# LUPA_uZED.net
KiCad netlist of a schematic drawn in EAGLE
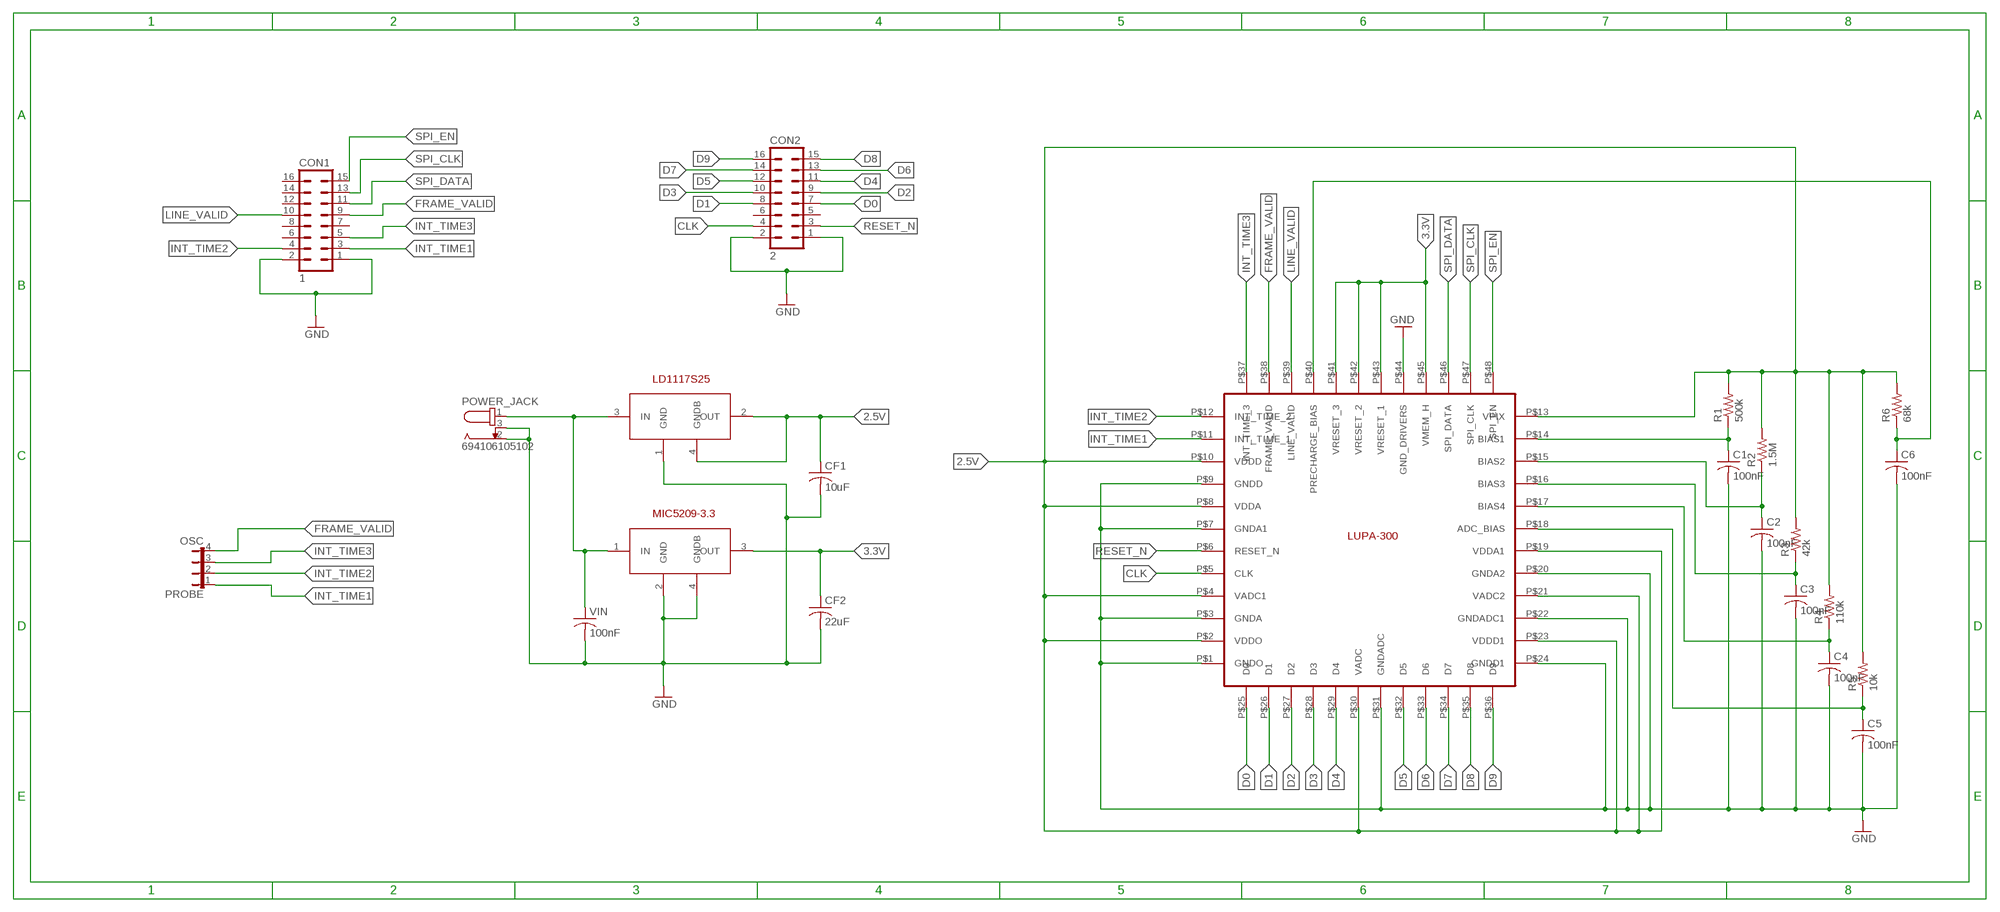
[diagram p0: schematic, sheet 1]

(export (version "E")
  (design (tool "Eeschema 10.0.6"))
  (components
    (comp (ref "C1")
      (value "100nF")
      (footprint "eagle-import:C3216")
      (libsource (lib "eagle-import") (part "C-USC3216"))
    )
    (comp (ref "C2")
      (value "100nF")
      (footprint "eagle-import:C3216")
      (libsource (lib "eagle-import") (part "C-USC3216"))
    )
    (comp (ref "C3")
      (value "100nF")
      (footprint "eagle-import:C3216")
      (libsource (lib "eagle-import") (part "C-USC3216"))
    )
    (comp (ref "C4")
      (value "100nF")
      (footprint "eagle-import:C3216")
      (libsource (lib "eagle-import") (part "C-USC3216"))
    )
    (comp (ref "C5")
      (value "100nF")
      (footprint "eagle-import:C3216")
      (libsource (lib "eagle-import") (part "C-USC3216"))
    )
    (comp (ref "C6")
      (value "100nF")
      (footprint "eagle-import:C3216")
      (libsource (lib "eagle-import") (part "C-USC3216"))
    )
    (comp (ref "CF1")
      (value "10uF")
      (footprint "eagle-import:C3216")
      (libsource (lib "eagle-import") (part "C-USC3216"))
    )
    (comp (ref "CF2")
      (value "22uF")
      (footprint "eagle-import:C3216")
      (libsource (lib "eagle-import") (part "C-USC3216"))
    )
    (comp (ref "CON1")
      (value "1")
      (footprint "eagle-import:MA08-2")
      (libsource (lib "eagle-import") (part "MA08-2"))
    )
    (comp (ref "CON2")
      (value "2")
      (footprint "eagle-import:MA08-2")
      (libsource (lib "eagle-import") (part "MA08-2"))
    )
    (comp (ref "POWER_JACK")
      (value "694106105102")
      (footprint "eagle-import:694106105102")
      (libsource (lib "eagle-import") (part "694106105102"))
    )
    (comp (ref "PROBE")
      (value "OSC")
      (footprint "eagle-import:JP4")
      (libsource (lib "eagle-import") (part "JP4E"))
    )
    (comp (ref "R1")
      (value "500k")
      (footprint "eagle-import:R1206")
      (libsource (lib "eagle-import") (part "R-US_R1206"))
    )
    (comp (ref "R2")
      (value "1.5M")
      (footprint "eagle-import:R1206")
      (libsource (lib "eagle-import") (part "R-US_R1206"))
    )
    (comp (ref "R3")
      (value "42k")
      (footprint "eagle-import:R1206")
      (libsource (lib "eagle-import") (part "R-US_R1206"))
    )
    (comp (ref "R4")
      (value "110k")
      (footprint "eagle-import:R1206")
      (libsource (lib "eagle-import") (part "R-US_R1206"))
    )
    (comp (ref "R5")
      (value "10k")
      (footprint "eagle-import:R1206")
      (libsource (lib "eagle-import") (part "R-US_R1206"))
    )
    (comp (ref "R6")
      (value "68k")
      (footprint "eagle-import:R1206")
      (libsource (lib "eagle-import") (part "R-US_R1206"))
    )
    (comp (ref "U$1")
      (value "IS")
      (footprint "eagle-import:LUPA300")
      (libsource (lib "eagle-import") (part "LUPA300"))
    )
    (comp (ref "U$2")
      (value "LD1117S25")
      (footprint "eagle-import:SOT223")
      (libsource (lib "eagle-import") (part "LD1117S25"))
    )
    (comp (ref "U$3")
      (value "MIC5209-3.3")
      (footprint "eagle-import:SOT223")
      (libsource (lib "eagle-import") (part "MIC5209-3.3"))
    )
    (comp (ref "VIN")
      (value "100nF")
      (footprint "eagle-import:C3216")
      (libsource (lib "eagle-import") (part "C-USC3216"))
    )
  )
  (nets
    (net (code "1") (name "2.5V") (class "Default")
      (node (ref "CF1") (pin "1") (pinfunction "1_1") (pintype "passive"))
      (node (ref "R1") (pin "2") (pinfunction "2_2") (pintype "passive"))
      (node (ref "R2") (pin "2") (pinfunction "2_2") (pintype "passive"))
      (node (ref "R3") (pin "2") (pinfunction "2_2") (pintype "passive"))
      (node (ref "R4") (pin "2") (pinfunction "2_2") (pintype "passive"))
      (node (ref "R5") (pin "2") (pinfunction "2_2") (pintype "passive"))
      (node (ref "R6") (pin "2") (pinfunction "2_2") (pintype "passive"))
      (node (ref "U$1") (pin "P$10") (pinfunction "VDDD_P$10") (pintype "bidirectional"))
      (node (ref "U$1") (pin "P$13") (pinfunction "VPIX_P$13") (pintype "bidirectional"))
      (node (ref "U$1") (pin "P$19") (pinfunction "VDDA1_P$19") (pintype "bidirectional"))
      (node (ref "U$1") (pin "P$2") (pinfunction "VDDO_P$2") (pintype "bidirectional"))
      (node (ref "U$1") (pin "P$21") (pinfunction "VADC2_P$21") (pintype "bidirectional"))
      (node (ref "U$1") (pin "P$23") (pinfunction "VDDD1_P$23") (pintype "bidirectional"))
      (node (ref "U$1") (pin "P$30") (pinfunction "VADC_P$30") (pintype "bidirectional"))
      (node (ref "U$1") (pin "P$4") (pinfunction "VADC1_P$4") (pintype "bidirectional"))
      (node (ref "U$1") (pin "P$8") (pinfunction "VDDA_P$8") (pintype "bidirectional"))
      (node (ref "U$2") (pin "2") (pinfunction "OUT_2") (pintype "bidirectional"))
      (node (ref "U$2") (pin "4") (pinfunction "GNDB_4") (pintype "bidirectional"))
    )
    (net (code "2") (name "3.3V") (class "Default")
      (node (ref "CF2") (pin "1") (pinfunction "1_1") (pintype "passive"))
      (node (ref "U$1") (pin "P$41") (pinfunction "VRESET_3_P$41") (pintype "bidirectional"))
      (node (ref "U$1") (pin "P$42") (pinfunction "VRESET_2_P$42") (pintype "bidirectional"))
      (node (ref "U$1") (pin "P$43") (pinfunction "VRESET_1_P$43") (pintype "bidirectional"))
      (node (ref "U$1") (pin "P$45") (pinfunction "VMEM_H_P$45") (pintype "bidirectional"))
      (node (ref "U$3") (pin "3") (pinfunction "OUT_3") (pintype "bidirectional"))
    )
    (net (code "3") (name "CLK") (class "Default")
      (node (ref "CON2") (pin "4") (pinfunction "4_4") (pintype "passive"))
      (node (ref "U$1") (pin "P$5") (pinfunction "CLK_P$5") (pintype "bidirectional"))
    )
    (net (code "4") (name "D0") (class "Default")
      (node (ref "CON2") (pin "7") (pinfunction "7_7") (pintype "passive"))
      (node (ref "U$1") (pin "P$25") (pinfunction "D0_P$25") (pintype "bidirectional"))
    )
    (net (code "5") (name "D1") (class "Default")
      (node (ref "CON2") (pin "8") (pinfunction "8_8") (pintype "passive"))
      (node (ref "U$1") (pin "P$26") (pinfunction "D1_P$26") (pintype "bidirectional"))
    )
    (net (code "6") (name "D2") (class "Default")
      (node (ref "CON2") (pin "9") (pinfunction "9_9") (pintype "passive"))
      (node (ref "U$1") (pin "P$27") (pinfunction "D2_P$27") (pintype "bidirectional"))
    )
    (net (code "7") (name "D3") (class "Default")
      (node (ref "CON2") (pin "10") (pinfunction "10_10") (pintype "passive"))
      (node (ref "U$1") (pin "P$28") (pinfunction "D3_P$28") (pintype "bidirectional"))
    )
    (net (code "8") (name "D4") (class "Default")
      (node (ref "CON2") (pin "11") (pinfunction "11_11") (pintype "passive"))
      (node (ref "U$1") (pin "P$29") (pinfunction "D4_P$29") (pintype "bidirectional"))
    )
    (net (code "9") (name "D5") (class "Default")
      (node (ref "CON2") (pin "12") (pinfunction "12_12") (pintype "passive"))
      (node (ref "U$1") (pin "P$32") (pinfunction "D5_P$32") (pintype "bidirectional"))
    )
    (net (code "10") (name "D6") (class "Default")
      (node (ref "CON2") (pin "13") (pinfunction "13_13") (pintype "passive"))
      (node (ref "U$1") (pin "P$33") (pinfunction "D6_P$33") (pintype "bidirectional"))
    )
    (net (code "11") (name "D7") (class "Default")
      (node (ref "CON2") (pin "14") (pinfunction "14_14") (pintype "passive"))
      (node (ref "U$1") (pin "P$34") (pinfunction "D7_P$34") (pintype "bidirectional"))
    )
    (net (code "12") (name "D8") (class "Default")
      (node (ref "CON2") (pin "15") (pinfunction "15_15") (pintype "passive"))
      (node (ref "U$1") (pin "P$35") (pinfunction "D8_P$35") (pintype "bidirectional"))
    )
    (net (code "13") (name "D9") (class "Default")
      (node (ref "CON2") (pin "16") (pinfunction "16_16") (pintype "passive"))
      (node (ref "U$1") (pin "P$36") (pinfunction "D9_P$36") (pintype "bidirectional"))
    )
    (net (code "14") (name "FRAME_VALID") (class "Default")
      (node (ref "CON1") (pin "9") (pinfunction "9_9") (pintype "passive"))
      (node (ref "PROBE") (pin "4") (pinfunction "4_4") (pintype "passive"))
      (node (ref "U$1") (pin "P$38") (pinfunction "FRAME_VALID_P$38") (pintype "bidirectional"))
    )
    (net (code "15") (name "GND") (class "Default")
      (node (ref "C1") (pin "2") (pinfunction "2_2") (pintype "passive"))
      (node (ref "C2") (pin "2") (pinfunction "2_2") (pintype "passive"))
      (node (ref "C3") (pin "2") (pinfunction "2_2") (pintype "passive"))
      (node (ref "C4") (pin "2") (pinfunction "2_2") (pintype "passive"))
      (node (ref "C5") (pin "2") (pinfunction "2_2") (pintype "passive"))
      (node (ref "C6") (pin "2") (pinfunction "2_2") (pintype "passive"))
      (node (ref "CF1") (pin "2") (pinfunction "2_2") (pintype "passive"))
      (node (ref "CF2") (pin "2") (pinfunction "2_2") (pintype "passive"))
      (node (ref "CON1") (pin "1") (pinfunction "1_1") (pintype "passive"))
      (node (ref "CON1") (pin "2") (pinfunction "2_2") (pintype "passive"))
      (node (ref "CON2") (pin "1") (pinfunction "1_1") (pintype "passive"))
      (node (ref "CON2") (pin "2") (pinfunction "2_2") (pintype "passive"))
      (node (ref "POWER_JACK") (pin "2") (pinfunction "2_2") (pintype "passive"))
      (node (ref "POWER_JACK") (pin "3") (pinfunction "3_3") (pintype "passive"))
      (node (ref "U$1") (pin "P$1") (pinfunction "GNDO_P$1") (pintype "bidirectional"))
      (node (ref "U$1") (pin "P$20") (pinfunction "GNDA2_P$20") (pintype "bidirectional"))
      (node (ref "U$1") (pin "P$22") (pinfunction "GNDADC1_P$22") (pintype "bidirectional"))
      (node (ref "U$1") (pin "P$24") (pinfunction "GNDD1_P$24") (pintype "bidirectional"))
      (node (ref "U$1") (pin "P$3") (pinfunction "GNDA_P$3") (pintype "bidirectional"))
      (node (ref "U$1") (pin "P$31") (pinfunction "GNDADC_P$31") (pintype "bidirectional"))
      (node (ref "U$1") (pin "P$44") (pinfunction "GND_DRIVERS_P$44") (pintype "bidirectional"))
      (node (ref "U$1") (pin "P$7") (pinfunction "GNDA1_P$7") (pintype "bidirectional"))
      (node (ref "U$1") (pin "P$9") (pinfunction "GNDD_P$9") (pintype "bidirectional"))
      (node (ref "U$2") (pin "1") (pinfunction "GND_1") (pintype "bidirectional"))
      (node (ref "U$3") (pin "2") (pinfunction "GND_2") (pintype "bidirectional"))
      (node (ref "U$3") (pin "4") (pinfunction "GNDB_4") (pintype "bidirectional"))
      (node (ref "VIN") (pin "2") (pinfunction "2_2") (pintype "passive"))
    )
    (net (code "16") (name "INT_TIME1") (class "Default")
      (node (ref "CON1") (pin "3") (pinfunction "3_3") (pintype "passive"))
      (node (ref "PROBE") (pin "1") (pinfunction "1_1") (pintype "passive"))
      (node (ref "U$1") (pin "P$11") (pinfunction "INT_TIME_1_P$11") (pintype "bidirectional"))
    )
    (net (code "17") (name "INT_TIME2") (class "Default")
      (node (ref "CON1") (pin "4") (pinfunction "4_4") (pintype "passive"))
      (node (ref "PROBE") (pin "2") (pinfunction "2_2") (pintype "passive"))
      (node (ref "U$1") (pin "P$12") (pinfunction "INT_TIME_2_P$12") (pintype "bidirectional"))
    )
    (net (code "18") (name "INT_TIME3") (class "Default")
      (node (ref "CON1") (pin "5") (pinfunction "5_5") (pintype "passive"))
      (node (ref "PROBE") (pin "3") (pinfunction "3_3") (pintype "passive"))
      (node (ref "U$1") (pin "P$37") (pinfunction "INT_TIME_3_P$37") (pintype "bidirectional"))
    )
    (net (code "19") (name "LINE_VALID") (class "Default")
      (node (ref "CON1") (pin "10") (pinfunction "10_10") (pintype "passive"))
      (node (ref "U$1") (pin "P$39") (pinfunction "LINE_VALID_P$39") (pintype "bidirectional"))
    )
    (net (code "20") (name "Net-(U$1-ADC_BIAS)") (class "Default")
      (node (ref "C5") (pin "1") (pinfunction "1_1") (pintype "passive"))
      (node (ref "R5") (pin "1") (pinfunction "1_1") (pintype "passive"))
      (node (ref "U$1") (pin "P$18") (pinfunction "ADC_BIAS_P$18") (pintype "bidirectional"))
    )
    (net (code "21") (name "Net-(U$1-BIAS1)") (class "Default")
      (node (ref "C1") (pin "1") (pinfunction "1_1") (pintype "passive"))
      (node (ref "R1") (pin "1") (pinfunction "1_1") (pintype "passive"))
      (node (ref "U$1") (pin "P$14") (pinfunction "BIAS1_P$14") (pintype "bidirectional"))
    )
    (net (code "22") (name "Net-(U$1-BIAS2)") (class "Default")
      (node (ref "C2") (pin "1") (pinfunction "1_1") (pintype "passive"))
      (node (ref "R2") (pin "1") (pinfunction "1_1") (pintype "passive"))
      (node (ref "U$1") (pin "P$15") (pinfunction "BIAS2_P$15") (pintype "bidirectional"))
    )
    (net (code "23") (name "Net-(U$1-BIAS3)") (class "Default")
      (node (ref "C3") (pin "1") (pinfunction "1_1") (pintype "passive"))
      (node (ref "R3") (pin "1") (pinfunction "1_1") (pintype "passive"))
      (node (ref "U$1") (pin "P$16") (pinfunction "BIAS3_P$16") (pintype "bidirectional"))
    )
    (net (code "24") (name "Net-(U$1-BIAS4)") (class "Default")
      (node (ref "C4") (pin "1") (pinfunction "1_1") (pintype "passive"))
      (node (ref "R4") (pin "1") (pinfunction "1_1") (pintype "passive"))
      (node (ref "U$1") (pin "P$17") (pinfunction "BIAS4_P$17") (pintype "bidirectional"))
    )
    (net (code "25") (name "Net-(U$1-PRECHARGE_BIAS)") (class "Default")
      (node (ref "C6") (pin "1") (pinfunction "1_1") (pintype "passive"))
      (node (ref "R6") (pin "1") (pinfunction "1_1") (pintype "passive"))
      (node (ref "U$1") (pin "P$40") (pinfunction "PRECHARGE_BIAS_P$40") (pintype "bidirectional"))
    )
    (net (code "26") (name "Net-(U$2-IN)") (class "Default")
      (node (ref "POWER_JACK") (pin "1") (pinfunction "1_1") (pintype "passive"))
      (node (ref "U$2") (pin "3") (pinfunction "IN_3") (pintype "bidirectional"))
      (node (ref "U$3") (pin "1") (pinfunction "IN_1") (pintype "bidirectional"))
      (node (ref "VIN") (pin "1") (pinfunction "1_1") (pintype "passive"))
    )
    (net (code "27") (name "RESET_N") (class "Default")
      (node (ref "CON2") (pin "3") (pinfunction "3_3") (pintype "passive"))
      (node (ref "U$1") (pin "P$6") (pinfunction "RESET_N_P$6") (pintype "bidirectional"))
    )
    (net (code "28") (name "SPI_CLK") (class "Default")
      (node (ref "CON1") (pin "13") (pinfunction "13_13") (pintype "passive"))
      (node (ref "U$1") (pin "P$47") (pinfunction "SPI_CLK_P$47") (pintype "bidirectional"))
    )
    (net (code "29") (name "SPI_DATA") (class "Default")
      (node (ref "CON1") (pin "11") (pinfunction "11_11") (pintype "passive"))
      (node (ref "U$1") (pin "P$46") (pinfunction "SPI_DATA_P$46") (pintype "bidirectional"))
    )
    (net (code "30") (name "SPI_EN") (class "Default")
      (node (ref "CON1") (pin "15") (pinfunction "15_15") (pintype "passive"))
      (node (ref "U$1") (pin "P$48") (pinfunction "SPI_EN_P$48") (pintype "bidirectional"))
    )
    (net (code "31") (name "unconnected-(CON1-Pad6)") (class "Default")
      (node (ref "CON1") (pin "6") (pinfunction "6_6") (pintype "passive"))
    )
    (net (code "32") (name "unconnected-(CON1-Pad7)") (class "Default")
      (node (ref "CON1") (pin "7") (pinfunction "7_7") (pintype "passive"))
    )
    (net (code "33") (name "unconnected-(CON1-Pad8)") (class "Default")
      (node (ref "CON1") (pin "8") (pinfunction "8_8") (pintype "passive"))
    )
    (net (code "34") (name "unconnected-(CON1-Pad12)") (class "Default")
      (node (ref "CON1") (pin "12") (pinfunction "12_12") (pintype "passive"))
    )
    (net (code "35") (name "unconnected-(CON1-Pad14)") (class "Default")
      (node (ref "CON1") (pin "14") (pinfunction "14_14") (pintype "passive"))
    )
    (net (code "36") (name "unconnected-(CON1-Pad16)") (class "Default")
      (node (ref "CON1") (pin "16") (pinfunction "16_16") (pintype "passive"))
    )
    (net (code "37") (name "unconnected-(CON2-Pad5)") (class "Default")
      (node (ref "CON2") (pin "5") (pinfunction "5_5") (pintype "passive"))
    )
    (net (code "38") (name "unconnected-(CON2-Pad6)") (class "Default")
      (node (ref "CON2") (pin "6") (pinfunction "6_6") (pintype "passive"))
    )
  )
)
